# MotorDriver.net
KiCad netlist of a schematic drawn in EAGLE
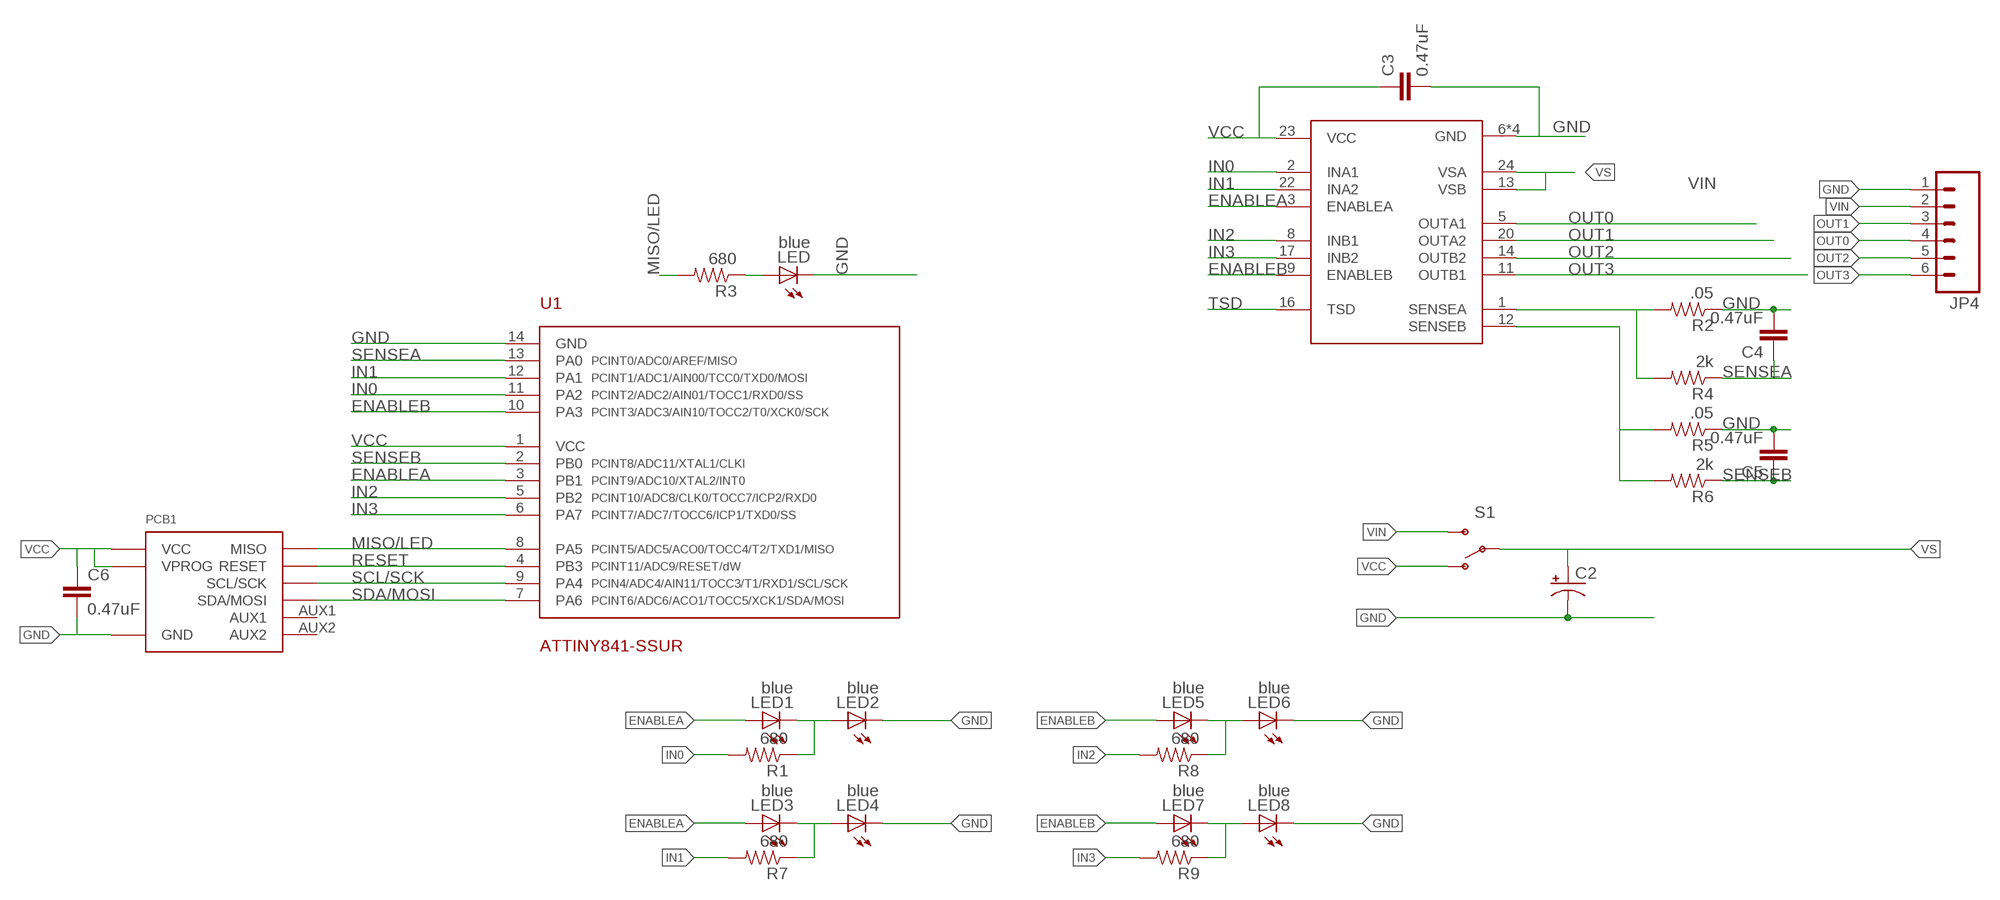
[diagram p0: schematic, sheet 1]

(export (version "E")
  (design (tool "Eeschema 10.0.6"))
  (components
    (comp (ref "C2")
      (value "CAP_POLC")
      (footprint "eagle-import:PANASONIC_C")
      (libsource (lib "eagle-import") (part "CAP_POLC"))
    )
    (comp (ref "C3")
      (value "0.47uF")
      (footprint "eagle-import:0805")
      (libsource (lib "eagle-import") (part "CAP0805"))
    )
    (comp (ref "C4")
      (value "0.47uF")
      (footprint "eagle-import:0805")
      (libsource (lib "eagle-import") (part "CAP0805"))
    )
    (comp (ref "C5")
      (value "0.47uF")
      (footprint "eagle-import:0805")
      (libsource (lib "eagle-import") (part "CAP0805"))
    )
    (comp (ref "C6")
      (value "0.47uF")
      (footprint "eagle-import:0805")
      (libsource (lib "eagle-import") (part "CAP0805"))
    )
    (comp (ref "JP4")
      (value "M063.5MM-6")
      (footprint "eagle-import:SCREWTERMINAL-3.5MM-6")
      (libsource (lib "eagle-import") (part "M063.5MM-6"))
    )
    (comp (ref "LED")
      (value "blue")
      (footprint "eagle-import:0805-LED")
      (fields (field (name "PARTNUM") "LTST-C171TBKT"))
      (libsource (lib "eagle-import") (part "LED-0805-BLUE"))
    )
    (comp (ref "LED1")
      (value "blue")
      (footprint "eagle-import:0805-LED")
      (fields (field (name "PARTNUM") "LTST-C171TBKT"))
      (libsource (lib "eagle-import") (part "LED-0805-BLUE"))
    )
    (comp (ref "LED2")
      (value "blue")
      (footprint "eagle-import:0805-LED")
      (fields (field (name "PARTNUM") "LTST-C171TBKT"))
      (libsource (lib "eagle-import") (part "LED-0805-BLUE"))
    )
    (comp (ref "LED3")
      (value "blue")
      (footprint "eagle-import:0805-LED")
      (fields (field (name "PARTNUM") "LTST-C171TBKT"))
      (libsource (lib "eagle-import") (part "LED-0805-BLUE"))
    )
    (comp (ref "LED4")
      (value "blue")
      (footprint "eagle-import:0805-LED")
      (fields (field (name "PARTNUM") "LTST-C171TBKT"))
      (libsource (lib "eagle-import") (part "LED-0805-BLUE"))
    )
    (comp (ref "LED5")
      (value "blue")
      (footprint "eagle-import:0805-LED")
      (fields (field (name "PARTNUM") "LTST-C171TBKT"))
      (libsource (lib "eagle-import") (part "LED-0805-BLUE"))
    )
    (comp (ref "LED6")
      (value "blue")
      (footprint "eagle-import:0805-LED")
      (fields (field (name "PARTNUM") "LTST-C171TBKT"))
      (libsource (lib "eagle-import") (part "LED-0805-BLUE"))
    )
    (comp (ref "LED7")
      (value "blue")
      (footprint "eagle-import:0805-LED")
      (fields (field (name "PARTNUM") "LTST-C171TBKT"))
      (libsource (lib "eagle-import") (part "LED-0805-BLUE"))
    )
    (comp (ref "LED8")
      (value "blue")
      (footprint "eagle-import:0805-LED")
      (fields (field (name "PARTNUM") "LTST-C171TBKT"))
      (libsource (lib "eagle-import") (part "LED-0805-BLUE"))
    )
    (comp (ref "PCB1")
      (value "MAGDEVICE-V2-DOUBLE")
      (footprint "eagle-import:MAGDEVICE-V2-DOUBLE")
      (libsource (lib "eagle-import") (part "MAGDEVICE-V2-DOUBLE"))
    )
    (comp (ref "R1")
      (value "680")
      (footprint "eagle-import:0805")
      (libsource (lib "eagle-import") (part "RESISTOR0805-RES"))
    )
    (comp (ref "R2")
      (value ".05")
      (footprint "eagle-import:0805")
      (libsource (lib "eagle-import") (part "RESISTOR0805-RES"))
    )
    (comp (ref "R3")
      (value "680")
      (footprint "eagle-import:0805")
      (libsource (lib "eagle-import") (part "RESISTOR0805-RES"))
    )
    (comp (ref "R4")
      (value "2k")
      (footprint "eagle-import:0805")
      (libsource (lib "eagle-import") (part "RESISTOR0805-RES"))
    )
    (comp (ref "R5")
      (value ".05")
      (footprint "eagle-import:0805")
      (libsource (lib "eagle-import") (part "RESISTOR0805-RES"))
    )
    (comp (ref "R6")
      (value "2k")
      (footprint "eagle-import:0805")
      (libsource (lib "eagle-import") (part "RESISTOR0805-RES"))
    )
    (comp (ref "R7")
      (value "680")
      (footprint "eagle-import:0805")
      (libsource (lib "eagle-import") (part "RESISTOR0805-RES"))
    )
    (comp (ref "R8")
      (value "680")
      (footprint "eagle-import:0805")
      (libsource (lib "eagle-import") (part "RESISTOR0805-RES"))
    )
    (comp (ref "R9")
      (value "680")
      (footprint "eagle-import:0805")
      (libsource (lib "eagle-import") (part "RESISTOR0805-RES"))
    )
    (comp (ref "S1")
      (value "SWITCH-SPDTPTH_LOCK")
      (footprint "eagle-import:SWITCH-SPDT_LOCK.007S")
      (libsource (lib "eagle-import") (part "SWITCH-SPDTPTH_LOCK"))
    )
    (comp (ref "U1")
      (value "ATTINY841-SSUR")
      (footprint "eagle-import:SOIC-14")
      (libsource (lib "eagle-import") (part "ATTINY841"))
    )
    (comp (ref "U2")
      (value "NJM2670")
      (footprint "eagle-import:SOP-24-E3")
      (libsource (lib "eagle-import") (part "NJM2670"))
    )
  )
  (nets
    (net (code "1") (name "/MISO{slash}LED") (class "Default")
      (node (ref "PCB1") (pin "MISO") (pinfunction "MISO_MISO") (pintype "bidirectional"))
      (node (ref "R3") (pin "2") (pinfunction "2_2") (pintype "passive"))
      (node (ref "U1") (pin "8") (pinfunction "PA5_8") (pintype "bidirectional"))
    )
    (net (code "2") (name "/RESET") (class "Default")
      (node (ref "PCB1") (pin "RESET") (pinfunction "RESET_RESET") (pintype "bidirectional"))
      (node (ref "U1") (pin "4") (pinfunction "PB3_4") (pintype "bidirectional"))
    )
    (net (code "3") (name "/SCL{slash}SCK") (class "Default")
      (node (ref "PCB1") (pin "SCL") (pinfunction "SCL/SCK_SCL") (pintype "bidirectional"))
      (node (ref "U1") (pin "9") (pinfunction "PA4_9") (pintype "bidirectional"))
    )
    (net (code "4") (name "/SDA{slash}MOSI") (class "Default")
      (node (ref "PCB1") (pin "SDA") (pinfunction "SDA/MOSI_SDA") (pintype "bidirectional"))
      (node (ref "U1") (pin "7") (pinfunction "PA6_7") (pintype "bidirectional"))
    )
    (net (code "5") (name "/SENSEA") (class "Default")
      (node (ref "C4") (pin "1") (pinfunction "1_1") (pintype "passive"))
      (node (ref "R4") (pin "1") (pinfunction "1_1") (pintype "passive"))
      (node (ref "U1") (pin "13") (pinfunction "PA0_13") (pintype "bidirectional"))
    )
    (net (code "6") (name "/SENSEB") (class "Default")
      (node (ref "C5") (pin "1") (pinfunction "1_1") (pintype "passive"))
      (node (ref "R6") (pin "1") (pinfunction "1_1") (pintype "passive"))
      (node (ref "U1") (pin "2") (pinfunction "PB0_2") (pintype "bidirectional"))
    )
    (net (code "7") (name "/TSD") (class "Default")
      (node (ref "U2") (pin "16") (pinfunction "TSD_16") (pintype "bidirectional"))
    )
    (net (code "8") (name "ENABLEA") (class "Default")
      (node (ref "LED1") (pin "A") (pinfunction "A_A") (pintype "passive"))
      (node (ref "LED3") (pin "A") (pinfunction "A_A") (pintype "passive"))
      (node (ref "U1") (pin "3") (pinfunction "PB1_3") (pintype "bidirectional"))
      (node (ref "U2") (pin "3") (pinfunction "ENABLEA_3") (pintype "bidirectional"))
    )
    (net (code "9") (name "ENABLEB") (class "Default")
      (node (ref "LED5") (pin "A") (pinfunction "A_A") (pintype "passive"))
      (node (ref "LED7") (pin "A") (pinfunction "A_A") (pintype "passive"))
      (node (ref "U1") (pin "10") (pinfunction "PA3_10") (pintype "bidirectional"))
      (node (ref "U2") (pin "9") (pinfunction "ENABLEB_9") (pintype "bidirectional"))
    )
    (net (code "10") (name "GND") (class "Default")
      (node (ref "C2") (pin "-") (pinfunction "-_-") (pintype "passive"))
      (node (ref "C3") (pin "2") (pinfunction "2_2") (pintype "passive"))
      (node (ref "C4") (pin "2") (pinfunction "2_2") (pintype "passive"))
      (node (ref "C5") (pin "2") (pinfunction "2_2") (pintype "passive"))
      (node (ref "C6") (pin "2") (pinfunction "2_2") (pintype "passive"))
      (node (ref "JP4") (pin "1") (pinfunction "1_1") (pintype "passive"))
      (node (ref "LED") (pin "C") (pinfunction "C_C") (pintype "passive"))
      (node (ref "LED2") (pin "C") (pinfunction "C_C") (pintype "passive"))
      (node (ref "LED4") (pin "C") (pinfunction "C_C") (pintype "passive"))
      (node (ref "LED6") (pin "C") (pinfunction "C_C") (pintype "passive"))
      (node (ref "LED8") (pin "C") (pinfunction "C_C") (pintype "passive"))
      (node (ref "PCB1") (pin "GND") (pinfunction "GND_GND") (pintype "bidirectional"))
      (node (ref "R2") (pin "1") (pinfunction "1_1") (pintype "passive"))
      (node (ref "R5") (pin "1") (pinfunction "1_1") (pintype "passive"))
      (node (ref "U1") (pin "14") (pinfunction "GND_14") (pintype "bidirectional"))
      (node (ref "U2") (pin "18") (pinfunction "GND_18") (pintype "bidirectional"))
      (node (ref "U2") (pin "19") (pinfunction "GND_19") (pintype "bidirectional"))
      (node (ref "U2") (pin "6") (pinfunction "GND_6") (pintype "bidirectional"))
      (node (ref "U2") (pin "7") (pinfunction "GND_7") (pintype "bidirectional"))
    )
    (net (code "11") (name "IN0") (class "Default")
      (node (ref "R1") (pin "2") (pinfunction "2_2") (pintype "passive"))
      (node (ref "U1") (pin "11") (pinfunction "PA2_11") (pintype "bidirectional"))
      (node (ref "U2") (pin "2") (pinfunction "INA1_2") (pintype "bidirectional"))
    )
    (net (code "12") (name "IN1") (class "Default")
      (node (ref "R7") (pin "2") (pinfunction "2_2") (pintype "passive"))
      (node (ref "U1") (pin "12") (pinfunction "PA1_12") (pintype "bidirectional"))
      (node (ref "U2") (pin "22") (pinfunction "INA2_22") (pintype "bidirectional"))
    )
    (net (code "13") (name "IN2") (class "Default")
      (node (ref "R8") (pin "2") (pinfunction "2_2") (pintype "passive"))
      (node (ref "U1") (pin "5") (pinfunction "PB2_5") (pintype "bidirectional"))
      (node (ref "U2") (pin "8") (pinfunction "INB1_8") (pintype "bidirectional"))
    )
    (net (code "14") (name "IN3") (class "Default")
      (node (ref "R9") (pin "2") (pinfunction "2_2") (pintype "passive"))
      (node (ref "U1") (pin "6") (pinfunction "PA7_6") (pintype "bidirectional"))
      (node (ref "U2") (pin "17") (pinfunction "INB2_17") (pintype "bidirectional"))
    )
    (net (code "15") (name "Net-(LED-PadA)") (class "Default")
      (node (ref "LED") (pin "A") (pinfunction "A_A") (pintype "passive"))
      (node (ref "R3") (pin "1") (pinfunction "1_1") (pintype "passive"))
    )
    (net (code "16") (name "Net-(LED1-PadC)") (class "Default")
      (node (ref "LED1") (pin "C") (pinfunction "C_C") (pintype "passive"))
      (node (ref "LED2") (pin "A") (pinfunction "A_A") (pintype "passive"))
      (node (ref "R1") (pin "1") (pinfunction "1_1") (pintype "passive"))
    )
    (net (code "17") (name "Net-(LED3-PadC)") (class "Default")
      (node (ref "LED3") (pin "C") (pinfunction "C_C") (pintype "passive"))
      (node (ref "LED4") (pin "A") (pinfunction "A_A") (pintype "passive"))
      (node (ref "R7") (pin "1") (pinfunction "1_1") (pintype "passive"))
    )
    (net (code "18") (name "Net-(LED5-PadC)") (class "Default")
      (node (ref "LED5") (pin "C") (pinfunction "C_C") (pintype "passive"))
      (node (ref "LED6") (pin "A") (pinfunction "A_A") (pintype "passive"))
      (node (ref "R8") (pin "1") (pinfunction "1_1") (pintype "passive"))
    )
    (net (code "19") (name "Net-(LED7-PadC)") (class "Default")
      (node (ref "LED7") (pin "C") (pinfunction "C_C") (pintype "passive"))
      (node (ref "LED8") (pin "A") (pinfunction "A_A") (pintype "passive"))
      (node (ref "R9") (pin "1") (pinfunction "1_1") (pintype "passive"))
    )
    (net (code "20") (name "Net-(U2-SENSEA)") (class "Default")
      (node (ref "R2") (pin "2") (pinfunction "2_2") (pintype "passive"))
      (node (ref "R4") (pin "2") (pinfunction "2_2") (pintype "passive"))
      (node (ref "U2") (pin "1") (pinfunction "SENSEA_1") (pintype "bidirectional"))
    )
    (net (code "21") (name "Net-(U2-SENSEB)") (class "Default")
      (node (ref "R5") (pin "2") (pinfunction "2_2") (pintype "passive"))
      (node (ref "R6") (pin "2") (pinfunction "2_2") (pintype "passive"))
      (node (ref "U2") (pin "12") (pinfunction "SENSEB_12") (pintype "bidirectional"))
    )
    (net (code "22") (name "OUT0") (class "Default")
      (node (ref "JP4") (pin "4") (pinfunction "4_4") (pintype "passive"))
      (node (ref "U2") (pin "5") (pinfunction "OUTA1_5") (pintype "bidirectional"))
    )
    (net (code "23") (name "OUT1") (class "Default")
      (node (ref "JP4") (pin "3") (pinfunction "3_3") (pintype "passive"))
      (node (ref "U2") (pin "20") (pinfunction "OUTA2_20") (pintype "bidirectional"))
    )
    (net (code "24") (name "OUT2") (class "Default")
      (node (ref "JP4") (pin "5") (pinfunction "5_5") (pintype "passive"))
      (node (ref "U2") (pin "14") (pinfunction "OUTB2_14") (pintype "bidirectional"))
    )
    (net (code "25") (name "OUT3") (class "Default")
      (node (ref "JP4") (pin "6") (pinfunction "6_6") (pintype "passive"))
      (node (ref "U2") (pin "11") (pinfunction "OUTB1_11") (pintype "bidirectional"))
    )
    (net (code "26") (name "VCC") (class "Default")
      (node (ref "C3") (pin "1") (pinfunction "1_1") (pintype "passive"))
      (node (ref "C6") (pin "1") (pinfunction "1_1") (pintype "passive"))
      (node (ref "PCB1") (pin "VCC") (pinfunction "VCC_VCC") (pintype "bidirectional"))
      (node (ref "PCB1") (pin "VPROG") (pinfunction "VPROG_VPROG") (pintype "bidirectional"))
      (node (ref "S1") (pin "1") (pinfunction "O_1") (pintype "passive"))
      (node (ref "U1") (pin "1") (pinfunction "VCC_1") (pintype "bidirectional"))
      (node (ref "U2") (pin "23") (pinfunction "VCC_23") (pintype "bidirectional"))
    )
    (net (code "27") (name "VIN") (class "Default")
      (node (ref "JP4") (pin "2") (pinfunction "2_2") (pintype "passive"))
      (node (ref "S1") (pin "3") (pinfunction "S_3") (pintype "passive"))
    )
    (net (code "28") (name "VS") (class "Default")
      (node (ref "C2") (pin "+") (pinfunction "+_+") (pintype "passive"))
      (node (ref "S1") (pin "2") (pinfunction "P_2") (pintype "passive"))
      (node (ref "U2") (pin "13") (pinfunction "VSB_13") (pintype "bidirectional"))
      (node (ref "U2") (pin "24") (pinfunction "VSA_24") (pintype "bidirectional"))
    )
    (net (code "29") (name "unconnected-(PCB1-PadAUX1)") (class "Default")
      (node (ref "PCB1") (pin "AUX1") (pinfunction "AUX1_AUX1") (pintype "bidirectional"))
    )
    (net (code "30") (name "unconnected-(PCB1-PadAUX2)") (class "Default")
      (node (ref "PCB1") (pin "AUX2") (pinfunction "AUX2_AUX2") (pintype "bidirectional"))
    )
  )
)
